# Neopixel.net
KiCad netlist of a schematic drawn in Altium Designer
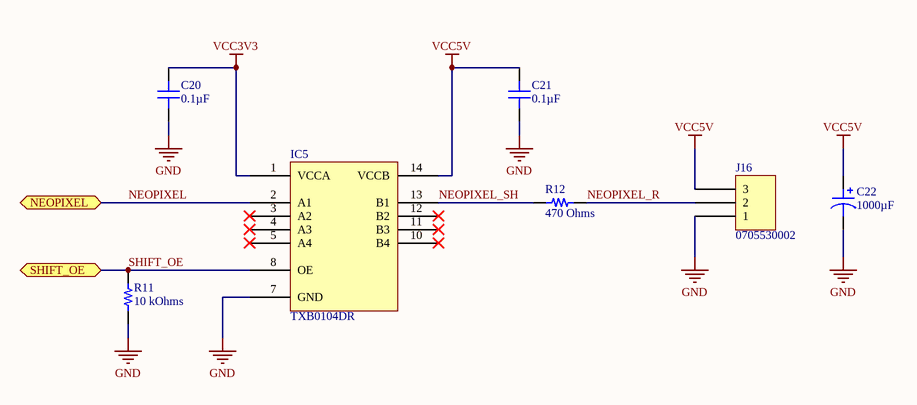
[diagram p0: Neopixel.SchDoc]

(export (version "E")
  (design (tool "Eeschema 10.0.6"))
  (components
    (comp (ref "C20")
      (value "0.1µF")
      (footprint "CAP 0402_1005")
      (description "CAP CER 0402 0.1UF 16V X7R 10%")
      (fields (field (name "PART NUMBER") "C0402C104K4RECAUTO") (field (name "MANUFACTURER") "KEMET"))
      (libsource (lib "CAL") (part "Capacitor"))
    )
    (comp (ref "C21")
      (value "0.1µF")
      (footprint "CAP 0402_1005")
      (description "CAP CER 0402 0.1UF 16V X7R 10%")
      (fields (field (name "PART NUMBER") "C0402C104K4RECAUTO") (field (name "MANUFACTURER") "KEMET"))
      (libsource (lib "CAL") (part "Capacitor"))
    )
    (comp (ref "C22")
      (value "1000µF")
      (footprint "CAP ALSMD 8.3MM H10.5MM")
      (description "CAP ALUM 1000UF 20% 10V SMD")
      (fields
        (field (name "PART NUMBER") "EEE-FT1A102AP")
        (field (name "MANUFACTURER") "Panasonic Electronic Components")
      )
      (libsource (lib "CAL") (part "Polarised Capacitor"))
    )
    (comp (ref "IC5")
      (value "TXB0104DR")
      (footprint "TI SOIC-14 D")
      (description "IC TRNSLTR BIDIRECTIONAL 14SOIC")
      (libsource (lib "CAL") (part "TI TXB0104"))
    )
    (comp (ref "J16")
      (value "0705530002")
      (footprint "MOLEX SDA-70553-3PIN")
      (description "CONN HEADER R/A 3POS 2.54MM")
      (fields (field (name "MANUFACTURER") "Molex"))
      (libsource (lib "Celestial") (part "3 Pin"))
    )
    (comp (ref "R11")
      (value "10 kOhms")
      (footprint "RES 0402_1005")
      (description "RES SMD 10K OHM 0.1% 1/16W 0402")
      (fields
        (field (name "PART NUMBER") "CPF0402B10KE1")
        (field (name "MANUFACTURER") "TE Connectivity Passive Product")
      )
      (libsource (lib "Celestial") (part "Resistor"))
    )
    (comp (ref "R12")
      (value "470 Ohms")
      (footprint "RES 0402_1005")
      (description "RES SMD 470 OHM 1% 1/5W 0402")
      (fields (field (name "PART NUMBER") "RCS0402470RFKED") (field (name "MANUFACTURER") "Vishay Dale"))
      (libsource (lib "CAL") (part "Resistor"))
    )
  )
  (nets
    (net (code "1") (name "/NEOPIXEL") (class "Default")
      (node (ref "IC5") (pin "2") (pinfunction "A1_2") (pintype "passive"))
    )
    (net (code "2") (name "/NEOPIXEL_R") (class "Default")
      (node (ref "J16") (pin "2") (pinfunction "2_2") (pintype "passive"))
      (node (ref "R12") (pin "2") (pinfunction "2_2") (pintype "passive"))
    )
    (net (code "3") (name "/NEOPIXEL_SH") (class "Default")
      (node (ref "IC5") (pin "13") (pinfunction "B1_13") (pintype "passive"))
      (node (ref "R12") (pin "1") (pinfunction "1_1") (pintype "passive"))
    )
    (net (code "4") (name "/SHIFT_OE") (class "Default")
      (node (ref "IC5") (pin "8") (pinfunction "OE_8") (pintype "passive"))
      (node (ref "R11") (pin "2") (pinfunction "2_2") (pintype "passive"))
    )
    (net (code "5") (name "GND") (class "Default")
      (node (ref "C20") (pin "1") (pinfunction "1_1") (pintype "passive"))
      (node (ref "C21") (pin "1") (pinfunction "1_1") (pintype "passive"))
      (node (ref "C22") (pin "2") (pinfunction "2_2") (pintype "passive"))
      (node (ref "IC5") (pin "7") (pinfunction "GND_7") (pintype "passive"))
      (node (ref "J16") (pin "1") (pinfunction "1_1") (pintype "passive"))
      (node (ref "R11") (pin "1") (pinfunction "1_1") (pintype "passive"))
    )
    (net (code "6") (name "VCC3V3") (class "Default")
      (node (ref "C20") (pin "2") (pinfunction "2_2") (pintype "passive"))
      (node (ref "IC5") (pin "1") (pinfunction "VCCA_1") (pintype "passive"))
    )
    (net (code "7") (name "VCC5V") (class "Default")
      (node (ref "C21") (pin "2") (pinfunction "2_2") (pintype "passive"))
      (node (ref "C22") (pin "1") (pinfunction "1_1") (pintype "passive"))
      (node (ref "IC5") (pin "14") (pinfunction "VCCB_14") (pintype "passive"))
      (node (ref "J16") (pin "3") (pinfunction "3_3") (pintype "passive"))
    )
    (net (code "8") (name "unconnected-(IC5-A2-Pad3)") (class "Default")
      (node (ref "IC5") (pin "3") (pinfunction "A2_3") (pintype "passive+no_connect"))
    )
    (net (code "9") (name "unconnected-(IC5-A3-Pad4)") (class "Default")
      (node (ref "IC5") (pin "4") (pinfunction "A3_4") (pintype "passive+no_connect"))
    )
    (net (code "10") (name "unconnected-(IC5-A4-Pad5)") (class "Default")
      (node (ref "IC5") (pin "5") (pinfunction "A4_5") (pintype "passive+no_connect"))
    )
    (net (code "11") (name "unconnected-(IC5-B2-Pad12)") (class "Default")
      (node (ref "IC5") (pin "12") (pinfunction "B2_12") (pintype "passive+no_connect"))
    )
    (net (code "12") (name "unconnected-(IC5-B3-Pad11)") (class "Default")
      (node (ref "IC5") (pin "11") (pinfunction "B3_11") (pintype "passive+no_connect"))
    )
    (net (code "13") (name "unconnected-(IC5-B4-Pad10)") (class "Default")
      (node (ref "IC5") (pin "10") (pinfunction "B4_10") (pintype "passive+no_connect"))
    )
  )
)
